# SCH_Stimulus-FSR402-RPF602_2026-07-22.net
KiCad netlist of a schematic drawn in EasyEDA
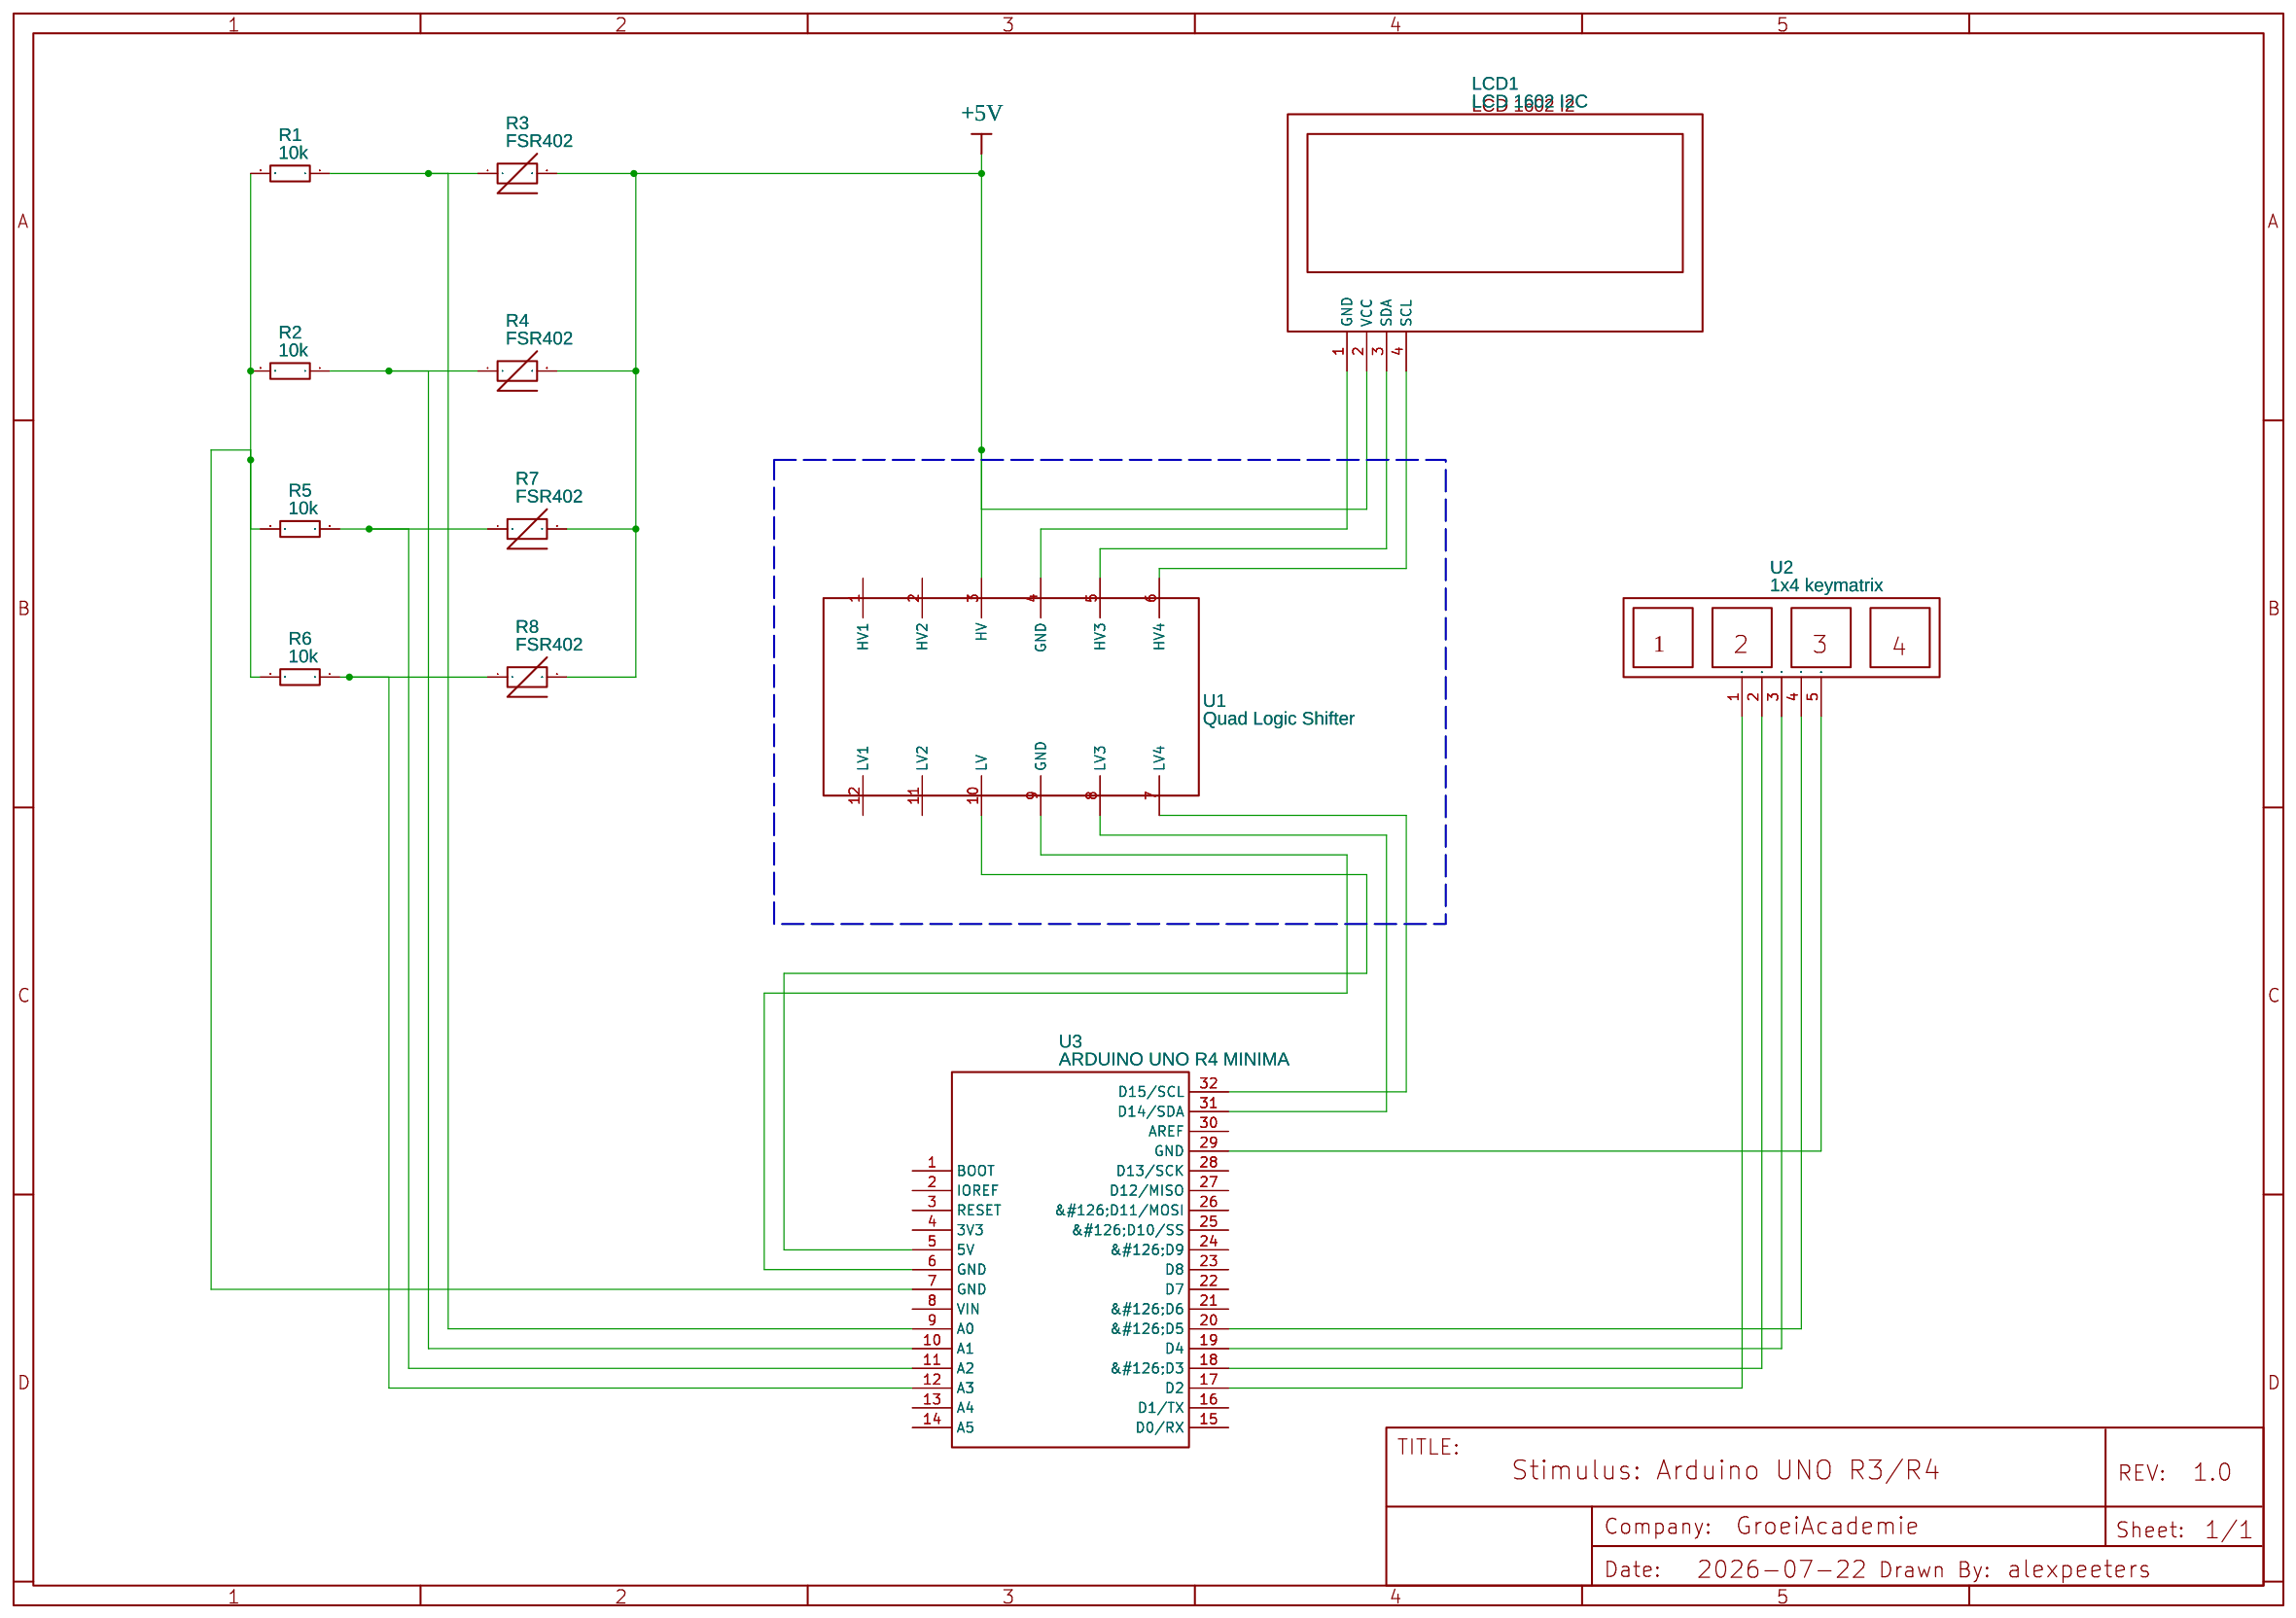
[diagram p0: schematic sheet]

(export (version "E")
  (design (tool "Eeschema 10.0.6"))
  (components
    (comp (ref "LCD1") (value "LCD 1602 I2C") (libsource (lib "") (part "I2CLCD16X2_N")))
    (comp (ref "R1")
      (value "10k")
      (fields (field (name "Manufacturer") "Made in China"))
      (libsource (lib "") (part "330Ω (331) ±5%"))
    )
    (comp (ref "R2")
      (value "10k")
      (fields (field (name "Manufacturer") "Made in China"))
      (libsource (lib "") (part "330Ω (331) ±5%"))
    )
    (comp (ref "R3") (value "FSR402") (libsource (lib "") (part "FSR402-OPCION1")))
    (comp (ref "R4") (value "FSR402") (libsource (lib "") (part "FSR402-OPCION1")))
    (comp (ref "R5")
      (value "10k")
      (fields (field (name "Manufacturer") "Made in China"))
      (libsource (lib "") (part "330Ω (331) ±5%"))
    )
    (comp (ref "R6")
      (value "10k")
      (fields (field (name "Manufacturer") "Made in China"))
      (libsource (lib "") (part "330Ω (331) ±5%"))
    )
    (comp (ref "R7") (value "FSR402") (libsource (lib "") (part "FSR402-OPCION1")))
    (comp (ref "R8") (value "FSR402") (libsource (lib "") (part "FSR402-OPCION1")))
    (comp (ref "U1") (value "Quad Logic Shifter") (libsource (lib "") (part "Quad Logic Shifter")))
    (comp (ref "U2") (value "1x4 keymatrix") (libsource (lib "") (part "Клавиатура 4*4")))
    (comp (ref "U3") (value "ARDUINO UNO R4 MINIMA") (libsource (lib "") (part "ARDUINO UNO R4 MINIMA")))
  )
  (nets
    (net (code "1") (name "+5V") (class "Default")
      (node (ref "LCD1") (pin "2") (pinfunction "VCC_2") (pintype "unspecified"))
      (node (ref "R3") (pin "2") (pinfunction "2_2") (pintype "unspecified"))
      (node (ref "R4") (pin "2") (pinfunction "2_2") (pintype "unspecified"))
      (node (ref "R7") (pin "2") (pinfunction "2_2") (pintype "unspecified"))
      (node (ref "R8") (pin "2") (pinfunction "2_2") (pintype "unspecified"))
      (node (ref "U1") (pin "3") (pinfunction "HV_3") (pintype "unspecified"))
    )
    (net (code "2") (name "Net-(LCD1-GND)") (class "Default")
      (node (ref "LCD1") (pin "1") (pinfunction "GND_1") (pintype "unspecified"))
      (node (ref "U1") (pin "4") (pinfunction "GND_4") (pintype "unspecified"))
    )
    (net (code "3") (name "Net-(LCD1-SCL)") (class "Default")
      (node (ref "LCD1") (pin "4") (pinfunction "SCL_4") (pintype "unspecified"))
      (node (ref "U1") (pin "6") (pinfunction "HV4_6") (pintype "unspecified"))
    )
    (net (code "4") (name "Net-(LCD1-SDA)") (class "Default")
      (node (ref "LCD1") (pin "3") (pinfunction "SDA_3") (pintype "unspecified"))
      (node (ref "U1") (pin "5") (pinfunction "HV3_5") (pintype "unspecified"))
    )
    (net (code "5") (name "Net-(R1-Pad2)") (class "Default")
      (node (ref "R1") (pin "2") (pinfunction "2_2") (pintype "unspecified"))
      (node (ref "R2") (pin "2") (pinfunction "2_2") (pintype "unspecified"))
      (node (ref "R5") (pin "2") (pinfunction "2_2") (pintype "unspecified"))
      (node (ref "R6") (pin "2") (pinfunction "2_2") (pintype "unspecified"))
      (node (ref "U3") (pin "7") (pinfunction "GND_7") (pintype "unspecified"))
    )
    (net (code "6") (name "Net-(U1-GND-Pad9)") (class "Default")
      (node (ref "U1") (pin "9") (pinfunction "GND_9") (pintype "unspecified"))
      (node (ref "U3") (pin "6") (pinfunction "GND_6") (pintype "unspecified"))
    )
    (net (code "7") (name "Net-(U1-LV)") (class "Default")
      (node (ref "U1") (pin "10") (pinfunction "LV_10") (pintype "unspecified"))
      (node (ref "U3") (pin "5") (pinfunction "5V_5") (pintype "unspecified"))
    )
    (net (code "8") (name "Net-(U1-LV3)") (class "Default")
      (node (ref "U1") (pin "8") (pinfunction "LV3_8") (pintype "unspecified"))
      (node (ref "U3") (pin "31") (pinfunction "D14/SDA_31") (pintype "unspecified"))
    )
    (net (code "9") (name "Net-(U1-LV4)") (class "Default")
      (node (ref "U1") (pin "7") (pinfunction "LV4_7") (pintype "unspecified"))
      (node (ref "U3") (pin "32") (pinfunction "D15/SCL_32") (pintype "unspecified"))
    )
    (net (code "10") (name "Net-(U2-C1)") (class "Default")
      (node (ref "U2") (pin "1") (pinfunction "C1_1") (pintype "unspecified"))
      (node (ref "U3") (pin "17") (pinfunction "D2_17") (pintype "unspecified"))
    )
    (net (code "11") (name "Net-(U2-C2)") (class "Default")
      (node (ref "U2") (pin "2") (pinfunction "C2_2") (pintype "unspecified"))
      (node (ref "U3") (pin "18") (pinfunction "&#126;D3_18") (pintype "unspecified"))
    )
    (net (code "12") (name "Net-(U2-C3)") (class "Default")
      (node (ref "U2") (pin "3") (pinfunction "C3_3") (pintype "unspecified"))
      (node (ref "U3") (pin "19") (pinfunction "D4_19") (pintype "unspecified"))
    )
    (net (code "13") (name "Net-(U2-R1)") (class "Default")
      (node (ref "U2") (pin "4") (pinfunction "R1_4") (pintype "unspecified"))
      (node (ref "U3") (pin "20") (pinfunction "&#126;D5_20") (pintype "unspecified"))
    )
    (net (code "14") (name "Net-(U2-R2)") (class "Default")
      (node (ref "U2") (pin "5") (pinfunction "R2_5") (pintype "unspecified"))
      (node (ref "U3") (pin "29") (pinfunction "GND_29") (pintype "unspecified"))
    )
    (net (code "15") (name "Net-(U3-A0)") (class "Default")
      (node (ref "R1") (pin "1") (pinfunction "1_1") (pintype "unspecified"))
      (node (ref "R3") (pin "1") (pinfunction "1_1") (pintype "unspecified"))
      (node (ref "U3") (pin "9") (pinfunction "A0_9") (pintype "unspecified"))
    )
    (net (code "16") (name "Net-(U3-A1)") (class "Default")
      (node (ref "R2") (pin "1") (pinfunction "1_1") (pintype "unspecified"))
      (node (ref "R4") (pin "1") (pinfunction "1_1") (pintype "unspecified"))
      (node (ref "U3") (pin "10") (pinfunction "A1_10") (pintype "unspecified"))
    )
    (net (code "17") (name "Net-(U3-A2)") (class "Default")
      (node (ref "R5") (pin "1") (pinfunction "1_1") (pintype "unspecified"))
      (node (ref "R7") (pin "1") (pinfunction "1_1") (pintype "unspecified"))
      (node (ref "U3") (pin "11") (pinfunction "A2_11") (pintype "unspecified"))
    )
    (net (code "18") (name "Net-(U3-A3)") (class "Default")
      (node (ref "R6") (pin "1") (pinfunction "1_1") (pintype "unspecified"))
      (node (ref "R8") (pin "1") (pinfunction "1_1") (pintype "unspecified"))
      (node (ref "U3") (pin "12") (pinfunction "A3_12") (pintype "unspecified"))
    )
    (net (code "19") (name "unconnected-(U1-HV1-Pad1)") (class "Default")
      (node (ref "U1") (pin "1") (pinfunction "HV1_1") (pintype "unspecified"))
    )
    (net (code "20") (name "unconnected-(U1-HV2-Pad2)") (class "Default")
      (node (ref "U1") (pin "2") (pinfunction "HV2_2") (pintype "unspecified"))
    )
    (net (code "21") (name "unconnected-(U1-LV1-Pad12)") (class "Default")
      (node (ref "U1") (pin "12") (pinfunction "LV1_12") (pintype "unspecified"))
    )
    (net (code "22") (name "unconnected-(U1-LV2-Pad11)") (class "Default")
      (node (ref "U1") (pin "11") (pinfunction "LV2_11") (pintype "unspecified"))
    )
    (net (code "23") (name "unconnected-(U3-&#126;D6-Pad21)") (class "Default")
      (node (ref "U3") (pin "21") (pinfunction "&#126;D6_21") (pintype "unspecified"))
    )
    (net (code "24") (name "unconnected-(U3-&#126;D9-Pad24)") (class "Default")
      (node (ref "U3") (pin "24") (pinfunction "&#126;D9_24") (pintype "unspecified"))
    )
    (net (code "25") (name "unconnected-(U3-&#126;D10{slash}SS-Pad25)") (class "Default")
      (node (ref "U3") (pin "25") (pinfunction "&#126;D10/SS_25") (pintype "unspecified"))
    )
    (net (code "26") (name "unconnected-(U3-&#126;D11{slash}MOSI-Pad26)") (class "Default")
      (node (ref "U3") (pin "26") (pinfunction "&#126;D11/MOSI_26") (pintype "unspecified"))
    )
    (net (code "27") (name "unconnected-(U3-3V3-Pad4)") (class "Default")
      (node (ref "U3") (pin "4") (pinfunction "3V3_4") (pintype "unspecified"))
    )
    (net (code "28") (name "unconnected-(U3-A4-Pad13)") (class "Default")
      (node (ref "U3") (pin "13") (pinfunction "A4_13") (pintype "unspecified"))
    )
    (net (code "29") (name "unconnected-(U3-A5-Pad14)") (class "Default")
      (node (ref "U3") (pin "14") (pinfunction "A5_14") (pintype "unspecified"))
    )
    (net (code "30") (name "unconnected-(U3-AREF-Pad30)") (class "Default")
      (node (ref "U3") (pin "30") (pinfunction "AREF_30") (pintype "unspecified"))
    )
    (net (code "31") (name "unconnected-(U3-BOOT-Pad1)") (class "Default")
      (node (ref "U3") (pin "1") (pinfunction "BOOT_1") (pintype "unspecified"))
    )
    (net (code "32") (name "unconnected-(U3-D0{slash}RX-Pad15)") (class "Default")
      (node (ref "U3") (pin "15") (pinfunction "D0/RX_15") (pintype "unspecified"))
    )
    (net (code "33") (name "unconnected-(U3-D1{slash}TX-Pad16)") (class "Default")
      (node (ref "U3") (pin "16") (pinfunction "D1/TX_16") (pintype "unspecified"))
    )
    (net (code "34") (name "unconnected-(U3-D7-Pad22)") (class "Default")
      (node (ref "U3") (pin "22") (pinfunction "D7_22") (pintype "unspecified"))
    )
    (net (code "35") (name "unconnected-(U3-D8-Pad23)") (class "Default")
      (node (ref "U3") (pin "23") (pinfunction "D8_23") (pintype "unspecified"))
    )
    (net (code "36") (name "unconnected-(U3-D12{slash}MISO-Pad27)") (class "Default")
      (node (ref "U3") (pin "27") (pinfunction "D12/MISO_27") (pintype "unspecified"))
    )
    (net (code "37") (name "unconnected-(U3-D13{slash}SCK-Pad28)") (class "Default")
      (node (ref "U3") (pin "28") (pinfunction "D13/SCK_28") (pintype "unspecified"))
    )
    (net (code "38") (name "unconnected-(U3-IOREF-Pad2)") (class "Default")
      (node (ref "U3") (pin "2") (pinfunction "IOREF_2") (pintype "unspecified"))
    )
    (net (code "39") (name "unconnected-(U3-RESET-Pad3)") (class "Default")
      (node (ref "U3") (pin "3") (pinfunction "RESET_3") (pintype "unspecified"))
    )
    (net (code "40") (name "unconnected-(U3-VIN-Pad8)") (class "Default")
      (node (ref "U3") (pin "8") (pinfunction "VIN_8") (pintype "unspecified"))
    )
  )
)
